# high_voltage.net
KiCad netlist of a schematic drawn in EAGLE
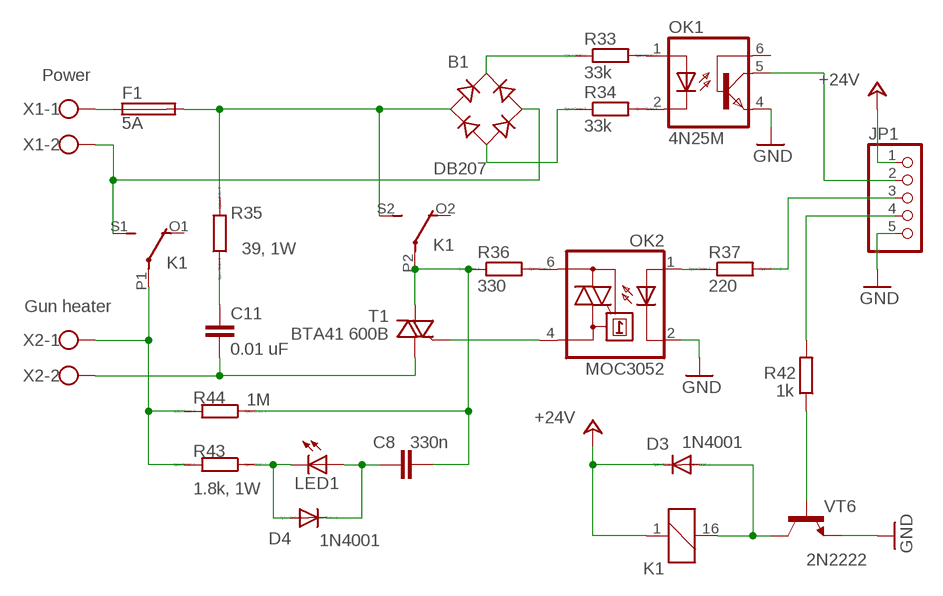
[diagram p0: schematic, sheet 1]

(export (version "E")
  (design (tool "Eeschema 10.0.6"))
  (components
    (comp (ref "B1")
      (value "DB207")
      (footprint "eagle-import:B-DIL")
      (libsource (lib "eagle-import") (part "B-DIL"))
    )
    (comp (ref "C8")
      (value "330n")
      (footprint "eagle-import:C025-025X050")
      (libsource (lib "eagle-import") (part "C-EU025-025X050"))
    )
    (comp (ref "C11")
      (value "0.01 uF")
      (footprint "eagle-import:C050-024X044")
      (libsource (lib "eagle-import") (part "C-EU050-024X044"))
    )
    (comp (ref "D3")
      (value "1N4001")
      (footprint "eagle-import:DO41-10")
      (libsource (lib "eagle-import") (part "1N4004"))
    )
    (comp (ref "D4")
      (value "1N4001")
      (footprint "eagle-import:DO41-10")
      (libsource (lib "eagle-import") (part "1N4004"))
    )
    (comp (ref "F1")
      (value "5A")
      (footprint "eagle-import:TE5")
      (libsource (lib "eagle-import") (part "TE5"))
    )
    (comp (ref "JP1")
      (value "PINHD-1X5/90")
      (footprint "eagle-import:1X05_90")
      (libsource (lib "eagle-import") (part "PINHD-1X5/90"))
    )
    (comp (ref "K1")
      (value "351")
      (footprint "eagle-import:351")
      (libsource (lib "eagle-import") (part "351"))
    )
    (comp (ref "LED1")
      (value "LED-3MM-NO_SILK")
      (footprint "eagle-import:LED3MM-NS")
      (libsource (lib "eagle-import") (part "LED-3MM-NO_SILK"))
    )
    (comp (ref "OK1")
      (value "4N25M")
      (footprint "eagle-import:DIL06")
      (fields (field (name "MPN") "4N25-M"))
      (libsource (lib "eagle-import") (part "4N?M25"))
    )
    (comp (ref "OK2")
      (value "MOC3052")
      (footprint "eagle-import:DIL06")
      (fields (field (name "MF") "FAIRCHILD SEMICONDUCTOR") (field (name "MPN") "MOC3021-M"))
      (libsource (lib "eagle-import") (part "MOC30M21"))
    )
    (comp (ref "R33")
      (value "33k")
      (footprint "eagle-import:0204_7")
      (libsource (lib "eagle-import") (part "R0204/7"))
    )
    (comp (ref "R34")
      (value "33k")
      (footprint "eagle-import:0204_7")
      (libsource (lib "eagle-import") (part "R0204/7"))
    )
    (comp (ref "R35")
      (value "39, 1W")
      (footprint "eagle-import:0204_7")
      (libsource (lib "eagle-import") (part "R0204/7"))
    )
    (comp (ref "R36")
      (value "330")
      (footprint "eagle-import:0204_7")
      (libsource (lib "eagle-import") (part "R0204/7"))
    )
    (comp (ref "R37")
      (value "220")
      (footprint "eagle-import:0204_7")
      (libsource (lib "eagle-import") (part "R0204/7"))
    )
    (comp (ref "R42")
      (value "1k")
      (footprint "eagle-import:0204_5")
      (libsource (lib "eagle-import") (part "R-EU_0204/5"))
    )
    (comp (ref "R43")
      (value "1.8k, 1W")
      (footprint "eagle-import:0204_7")
      (libsource (lib "eagle-import") (part "R0204/7"))
    )
    (comp (ref "R44")
      (value "1M")
      (footprint "eagle-import:0204_7")
      (libsource (lib "eagle-import") (part "R0204/7"))
    )
    (comp (ref "T1")
      (value "BTA41 600B")
      (footprint "eagle-import:TOP3L-1")
      (libsource (lib "eagle-import") (part "BTA26-H"))
    )
    (comp (ref "VT6")
      (value "2N2222")
      (footprint "eagle-import:TO18")
      (libsource (lib "eagle-import") (part "2N2222"))
    )
    (comp (ref "X1")
      (value "Power")
      (footprint "eagle-import:W237-102")
      (fields (field (name "MPN") "237-102"))
      (libsource (lib "eagle-import") (part "W237-102"))
    )
    (comp (ref "X2")
      (value "Gun heater")
      (footprint "eagle-import:W237-102")
      (fields (field (name "MPN") "237-102"))
      (libsource (lib "eagle-import") (part "W237-102"))
    )
  )
  (nets
    (net (code "1") (name "+24V") (class "Default")
      (node (ref "D3") (pin "C") (pinfunction "C_C") (pintype "passive"))
      (node (ref "JP1") (pin "1") (pinfunction "1_1") (pintype "passive"))
      (node (ref "K1") (pin "1") (pinfunction "1_1") (pintype "passive"))
    )
    (net (code "2") (name "GND") (class "Default")
      (node (ref "JP1") (pin "5") (pinfunction "5_5") (pintype "passive"))
      (node (ref "OK1") (pin "4") (pinfunction "EMI_4") (pintype "passive"))
      (node (ref "OK2") (pin "2") (pinfunction "C_2") (pintype "passive"))
      (node (ref "VT6") (pin "1") (pinfunction "E_1") (pintype "passive"))
    )
    (net (code "3") (name "Net-(B1-Pad+)") (class "Default")
      (node (ref "B1") (pin "+") (pinfunction "+_+") (pintype "passive"))
      (node (ref "R33") (pin "1") (pinfunction "1_1") (pintype "passive"))
    )
    (net (code "4") (name "Net-(B1-Pad-)") (class "Default")
      (node (ref "B1") (pin "-") (pinfunction "-_-") (pintype "passive"))
      (node (ref "R34") (pin "1") (pinfunction "1_1") (pintype "passive"))
    )
    (net (code "5") (name "Net-(C8-Pad1)") (class "Default")
      (node (ref "C8") (pin "1") (pinfunction "1_1") (pintype "passive"))
      (node (ref "D4") (pin "C") (pinfunction "C_C") (pintype "passive"))
      (node (ref "LED1") (pin "A") (pinfunction "A_A") (pintype "passive"))
    )
    (net (code "6") (name "Net-(C11-Pad1)") (class "Default")
      (node (ref "C11") (pin "1") (pinfunction "1_1") (pintype "passive"))
      (node (ref "R35") (pin "1") (pinfunction "1_1") (pintype "passive"))
    )
    (net (code "7") (name "Net-(JP1-Pad3)") (class "Default")
      (node (ref "JP1") (pin "3") (pinfunction "3_3") (pintype "passive"))
      (node (ref "R37") (pin "2") (pinfunction "2_2") (pintype "passive"))
    )
    (net (code "8") (name "Net-(JP1-Pad4)") (class "Default")
      (node (ref "JP1") (pin "4") (pinfunction "4_4") (pintype "passive"))
      (node (ref "R42") (pin "2") (pinfunction "2_2") (pintype "passive"))
    )
    (net (code "9") (name "Net-(K1A-2)") (class "Default")
      (node (ref "D3") (pin "A") (pinfunction "A_A") (pintype "passive"))
      (node (ref "K1") (pin "16") (pinfunction "2_16") (pintype "passive"))
      (node (ref "VT6") (pin "3") (pinfunction "C_3") (pintype "passive"))
    )
    (net (code "10") (name "Net-(K1B-P)") (class "Default")
      (node (ref "K1") (pin "P1") (pinfunction "P_P1") (pintype "passive"))
      (node (ref "R43") (pin "2") (pinfunction "2_2") (pintype "passive"))
      (node (ref "R44") (pin "2") (pinfunction "2_2") (pintype "passive"))
      (node (ref "X2") (pin "1") (pinfunction "KL_1") (pintype "passive"))
    )
    (net (code "11") (name "Net-(K1B-S)") (class "Default")
      (node (ref "B1") (pin "AC2") (pinfunction "AC2_AC2") (pintype "passive"))
      (node (ref "K1") (pin "S1") (pinfunction "S_S1") (pintype "passive"))
      (node (ref "X1") (pin "2") (pinfunction "KL_2") (pintype "passive"))
    )
    (net (code "12") (name "Net-(K1C-P)") (class "Default")
      (node (ref "C8") (pin "2") (pinfunction "2_2") (pintype "passive"))
      (node (ref "K1") (pin "P2") (pinfunction "P_P2") (pintype "passive"))
      (node (ref "R36") (pin "1") (pinfunction "1_1") (pintype "passive"))
      (node (ref "R44") (pin "1") (pinfunction "1_1") (pintype "passive"))
      (node (ref "T1") (pin "A2") (pinfunction "A2_A2") (pintype "passive"))
    )
    (net (code "13") (name "Net-(K1C-S)") (class "Default")
      (node (ref "B1") (pin "AC1") (pinfunction "AC1_AC1") (pintype "passive"))
      (node (ref "F1") (pin "2") (pinfunction "2_2") (pintype "passive"))
      (node (ref "K1") (pin "S2") (pinfunction "S_S2") (pintype "passive"))
      (node (ref "R35") (pin "2") (pinfunction "2_2") (pintype "passive"))
    )
    (net (code "14") (name "Net-(LED1-C)") (class "Default")
      (node (ref "D4") (pin "A") (pinfunction "A_A") (pintype "passive"))
      (node (ref "LED1") (pin "K") (pinfunction "C_K") (pintype "passive"))
      (node (ref "R43") (pin "1") (pinfunction "1_1") (pintype "passive"))
    )
    (net (code "15") (name "Net-(OK1-A)") (class "Default")
      (node (ref "OK1") (pin "1") (pinfunction "A_1") (pintype "passive"))
      (node (ref "R33") (pin "2") (pinfunction "2_2") (pintype "passive"))
    )
    (net (code "16") (name "Net-(OK1-C)") (class "Default")
      (node (ref "OK1") (pin "2") (pinfunction "C_2") (pintype "passive"))
      (node (ref "R34") (pin "2") (pinfunction "2_2") (pintype "passive"))
    )
    (net (code "17") (name "Net-(OK1-COL)") (class "Default")
      (node (ref "JP1") (pin "2") (pinfunction "2_2") (pintype "passive"))
      (node (ref "OK1") (pin "5") (pinfunction "COL_5") (pintype "passive"))
    )
    (net (code "18") (name "Net-(OK2-A)") (class "Default")
      (node (ref "OK2") (pin "1") (pinfunction "A_1") (pintype "passive"))
      (node (ref "R37") (pin "1") (pinfunction "1_1") (pintype "passive"))
    )
    (net (code "19") (name "Net-(OK2-A1)") (class "Default")
      (node (ref "OK2") (pin "4") (pinfunction "A1_4") (pintype "passive"))
      (node (ref "T1") (pin "G") (pinfunction "G_G") (pintype "passive"))
    )
    (net (code "20") (name "Net-(OK2-A2)") (class "Default")
      (node (ref "OK2") (pin "6") (pinfunction "A2_6") (pintype "passive"))
      (node (ref "R36") (pin "2") (pinfunction "2_2") (pintype "passive"))
    )
    (net (code "21") (name "Net-(VT6-B)") (class "Default")
      (node (ref "R42") (pin "1") (pinfunction "1_1") (pintype "passive"))
      (node (ref "VT6") (pin "2") (pinfunction "B_2") (pintype "passive"))
    )
    (net (code "22") (name "Net-(X1A-KL)") (class "Default")
      (node (ref "F1") (pin "1") (pinfunction "1_1") (pintype "passive"))
      (node (ref "X1") (pin "1") (pinfunction "KL_1") (pintype "passive"))
    )
    (net (code "23") (name "Net-(X2B-KL)") (class "Default")
      (node (ref "C11") (pin "2") (pinfunction "2_2") (pintype "passive"))
      (node (ref "T1") (pin "A1") (pinfunction "A1_A1") (pintype "passive"))
      (node (ref "X2") (pin "2") (pinfunction "KL_2") (pintype "passive"))
    )
    (net (code "24") (name "unconnected-(K1B-O-PadO1)") (class "Default")
      (node (ref "K1") (pin "O1") (pinfunction "O_O1") (pintype "passive"))
    )
    (net (code "25") (name "unconnected-(K1C-O-PadO2)") (class "Default")
      (node (ref "K1") (pin "O2") (pinfunction "O_O2") (pintype "passive"))
    )
    (net (code "26") (name "unconnected-(OK1-BAS-Pad6)") (class "Default")
      (node (ref "OK1") (pin "6") (pinfunction "BAS_6") (pintype "passive"))
    )
  )
)
